# Schematic.net
KiCad netlist of a schematic drawn in Altium Designer
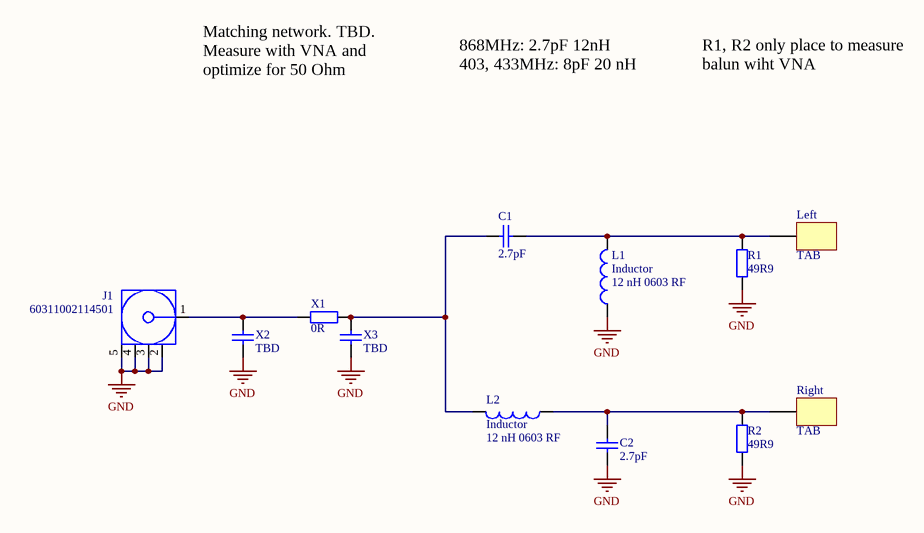
[diagram p0: Schematic.SchDoc]

(export (version "E")
  (design (tool "Eeschema 10.0.6"))
  (components
    (comp (ref "C1")
      (value "2.7pF")
      (footprint "CAPC0603N")
      (description "Multilayer Ceramic Capacitors MLCC - SMD/SMT 2.7pF 50V 0603 RoHS")
      (fields
        (field (name "MFR") "CL10C2R7CB8NNNC")
        (field (name "MANUFACTURER") "Samsung Electro-Mechanics")
      )
      (libsource (lib "MLCC") (part "Cap"))
    )
    (comp (ref "C2")
      (value "2.7pF")
      (footprint "CAPC0603N")
      (description "Multilayer Ceramic Capacitors MLCC - SMD/SMT 2.7pF 50V 0603 RoHS")
      (fields
        (field (name "MFR") "CL10C2R7CB8NNNC")
        (field (name "MANUFACTURER") "Samsung Electro-Mechanics")
      )
      (libsource (lib "MLCC") (part "Cap"))
    )
    (comp (ref "J1")
      (value "60311002114501")
      (footprint "60311002114501")
      (description "Rf Coax Conn, Sma R/A Jack, 50 Ohm, Pcb Rohs Compliant: Yes")
      (libsource (lib "Altium Content Vault") (part "Jack_4GND"))
    )
    (comp (ref "L1")
      (value "Inductor")
      (footprint "CAPC0603N")
      (fields (field (name "SCH") "12 nH 0603 RF"))
      (libsource (lib "WE-MK") (part "Inductor"))
    )
    (comp (ref "L2")
      (value "Inductor")
      (footprint "CAPC0603N")
      (fields (field (name "SCH") "12 nH 0603 RF"))
      (libsource (lib "WE-MK") (part "Inductor"))
    )
    (comp (ref "Left") (value "TAB") (footprint "TAB") (libsource (lib "LTO18650") (part "TAB")))
    (comp (ref "R1")
      (value "49R9")
      (footprint "RESC0603N")
      (description "Chip Resistor - Surface Mount 49.9Ohms ±1% 1/10W 0603 RoHS")
      (fields (field (name "Comment") "Res"))
      (libsource (lib "") (part "Res_1"))
    )
    (comp (ref "R2")
      (value "49R9")
      (footprint "RESC0603N")
      (description "Chip Resistor - Surface Mount 49.9Ohms ±1% 1/10W 0603 RoHS")
      (fields (field (name "Comment") "Res"))
      (libsource (lib "") (part "Res_1"))
    )
    (comp (ref "Right") (value "TAB") (footprint "TAB") (libsource (lib "LTO18650") (part "TAB")))
    (comp (ref "X1")
      (value "0R")
      (footprint "RESC0603N")
      (description "Chip Resistor - Surface Mount 0Ohms ±1% 1/10W 0603 RoHS")
      (fields (field (name "Comment") "Res"))
      (libsource (lib "JLCRES") (part "Res"))
    )
    (comp (ref "X2")
      (value "TBD")
      (footprint "CAPC0603N")
      (description "Multilayer Ceramic Capacitors MLCC - SMD/SMT 1pF 50V 0603 RoHS")
      (fields
        (field (name "MFR") "CL10C010CB8NNNC")
        (field (name "MANUFACTURER") "Samsung Electro-Mechanics")
      )
      (libsource (lib "MLCC") (part "Cap"))
    )
    (comp (ref "X3")
      (value "TBD")
      (footprint "CAPC0603N")
      (description "Multilayer Ceramic Capacitors MLCC - SMD/SMT 1pF 50V 0603 RoHS")
      (fields
        (field (name "MFR") "CL10C010CB8NNNC")
        (field (name "MANUFACTURER") "Samsung Electro-Mechanics")
      )
      (libsource (lib "MLCC") (part "Cap"))
    )
  )
  (nets
    (net (code "1") (name "GND") (class "Default")
      (node (ref "C2") (pin "1") (pinfunction "1_1") (pintype "passive"))
      (node (ref "J1") (pin "2") (pinfunction "GND_2") (pintype "passive"))
      (node (ref "J1") (pin "3") (pinfunction "GND_3") (pintype "passive"))
      (node (ref "J1") (pin "4") (pinfunction "GND_4") (pintype "passive"))
      (node (ref "J1") (pin "5") (pinfunction "GND_5") (pintype "passive"))
      (node (ref "L1") (pin "1") (pinfunction "1_1") (pintype "passive"))
      (node (ref "R1") (pin "1") (pinfunction "1_1") (pintype "passive"))
      (node (ref "R2") (pin "1") (pinfunction "1_1") (pintype "passive"))
      (node (ref "X2") (pin "1") (pinfunction "1_1") (pintype "passive"))
      (node (ref "X3") (pin "1") (pinfunction "1_1") (pintype "passive"))
    )
    (net (code "2") (name "Net-(C1-Pad1)") (class "Default")
      (node (ref "C1") (pin "1") (pinfunction "1_1") (pintype "passive"))
      (node (ref "L1") (pin "2") (pinfunction "2_2") (pintype "passive"))
      (node (ref "Left") (pin "1") (pinfunction "1_1") (pintype "passive"))
      (node (ref "R1") (pin "2") (pinfunction "2_2") (pintype "passive"))
    )
    (net (code "3") (name "Net-(C1-Pad2)") (class "Default")
      (node (ref "C1") (pin "2") (pinfunction "2_2") (pintype "passive"))
      (node (ref "L2") (pin "2") (pinfunction "2_2") (pintype "passive"))
      (node (ref "X1") (pin "2") (pinfunction "2_2") (pintype "passive"))
      (node (ref "X3") (pin "2") (pinfunction "2_2") (pintype "passive"))
    )
    (net (code "4") (name "Net-(C2-Pad2)") (class "Default")
      (node (ref "C2") (pin "2") (pinfunction "2_2") (pintype "passive"))
      (node (ref "L2") (pin "1") (pinfunction "1_1") (pintype "passive"))
      (node (ref "R2") (pin "2") (pinfunction "2_2") (pintype "passive"))
      (node (ref "Right") (pin "1") (pinfunction "1_1") (pintype "passive"))
    )
    (net (code "5") (name "Net-(J1-Signal)") (class "Default")
      (node (ref "J1") (pin "1") (pinfunction "Signal_1") (pintype "passive"))
      (node (ref "X1") (pin "1") (pinfunction "1_1") (pintype "passive"))
      (node (ref "X2") (pin "2") (pinfunction "2_2") (pintype "passive"))
    )
  )
)
